# Power_Supply_V1_1.net
KiCad netlist of a schematic drawn in Altium Designer
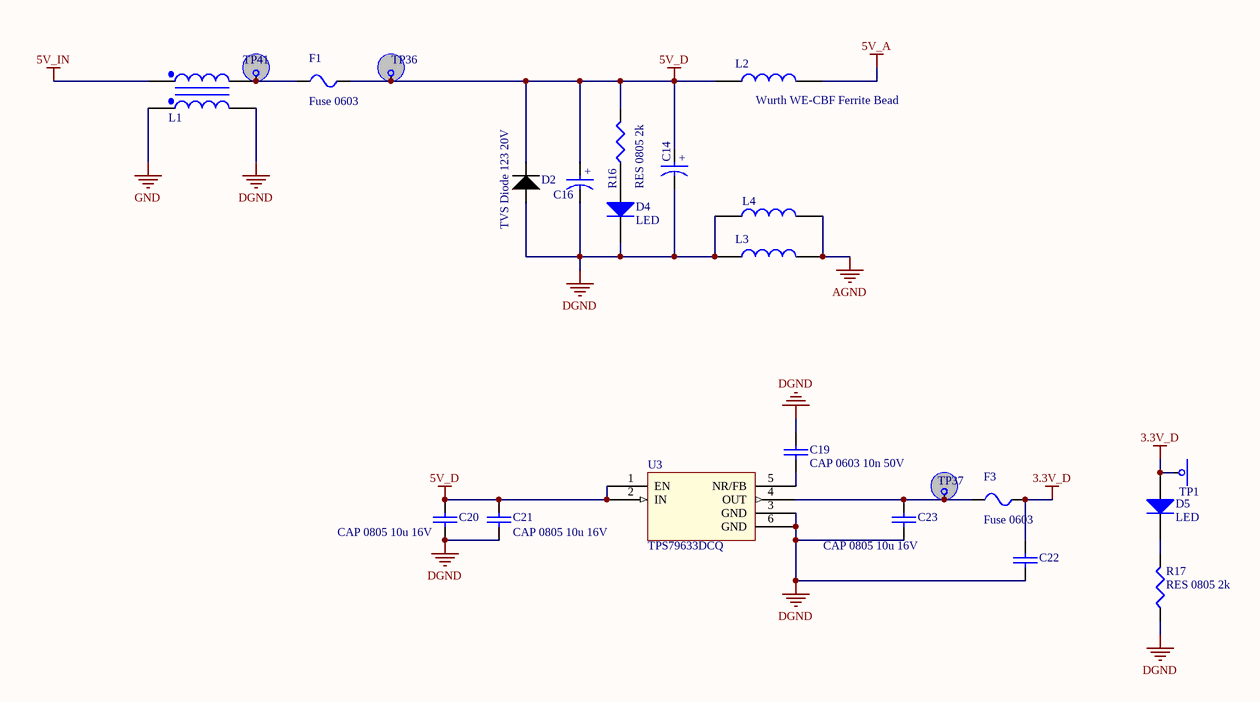
[diagram p0: Power_Supply_V1.1.SchDoc]

(export (version "E")
  (design (tool "Eeschema 10.0.6"))
  (components
    (comp (ref "C14")
      (value "Panasonic SMD aluminum cap FT V size d")
      (footprint "Panasonic TF V SMD size D cap")
      (libsource (lib "SMD_R&C_V1.0") (part "Panasonic SMD aluminum cap FT V size d"))
    )
    (comp (ref "C16")
      (value "Panasonic SMD aluminum cap FT V size d")
      (footprint "Panasonic TF V SMD size D cap")
      (libsource (lib "SMD_R&C_V1.0") (part "Panasonic SMD aluminum cap FT V size d"))
    )
    (comp (ref "C19")
      (value "CAP 0603 10n 50V")
      (footprint "CAPC1608N")
      (description "CAP 0603 TBD")
      (fields (field (name "PART#") "TBD"))
      (libsource (lib "SMD_R&C_V1.0") (part "CAP 0603 TBD"))
    )
    (comp (ref "C20")
      (value "CAP 0805 10u 16V")
      (footprint "CAPC2012N")
      (description "CAP 0805 TBD")
      (fields (field (name "PART#") "TBD"))
      (libsource (lib "SMD_R&C_V1.0") (part "CAP 0805 TBD"))
    )
    (comp (ref "C21")
      (value "CAP 0805 10u 16V")
      (footprint "CAPC2012N")
      (description "CAP 0805 TBD")
      (fields (field (name "PART#") "TBD"))
      (libsource (lib "SMD_R&C_V1.0") (part "CAP 0805 TBD"))
    )
    (comp (ref "C22")
      (value "CAP 0805 10u 16V")
      (footprint "CAPC2012N")
      (description "CAP 0805 TBD")
      (fields (field (name "PART#") "TBD"))
      (libsource (lib "SMD_R&C_V1.0") (part "CAP 0805 TBD"))
    )
    (comp (ref "C23")
      (value "CAP 0805 10u 16V")
      (footprint "CAPC2012N")
      (description "CAP 0805 TBD")
      (fields (field (name "PART#") "TBD"))
      (libsource (lib "SMD_R&C_V1.0") (part "CAP 0805 TBD"))
    )
    (comp (ref "D2")
      (value "TVS Diode 123 20V")
      (footprint "SOD-123")
      (libsource (lib "Power_Inductor&Diode_V1.0") (part "TVS Diode TBD"))
    )
    (comp (ref "D4")
      (value "LED")
      (footprint "LED1608N")
      (fields (field (name "PART#") "475-1406-1-ND"))
      (libsource (lib "SMD_R&C_V1.0") (part "LED"))
    )
    (comp (ref "D5")
      (value "LED")
      (footprint "LED1608N")
      (fields (field (name "PART#") "475-1406-1-ND"))
      (libsource (lib "SMD_R&C_V1.0") (part "LED"))
    )
    (comp (ref "F1")
      (value "Fuse 0603")
      (footprint "RES1608N")
      (libsource (lib "SMD_R&C_V1.0") (part "Fuse 0603"))
    )
    (comp (ref "F3")
      (value "Fuse 0603")
      (footprint "RES1608N")
      (libsource (lib "SMD_R&C_V1.0") (part "Fuse 0603"))
    )
    (comp (ref "L1")
      (value "Wurth")
      (footprint "WURTH WE-SL5")
      (description "Wurth WE-SL5 Common Mode Choke")
      (fields (field (name "PART NUMBER") "811-1253-ND") (field (name "MANUFACTURER PART NUMBER") "51105C"))
      (libsource (lib "Aarons_Library") (part "Wurth WE-SL5"))
    )
    (comp (ref "L2")
      (value "Wurth WE-CBF Ferrite Bead")
      (footprint "Wurth WE-CBF")
      (description "Wurth WE-CBF Ferrite Bead 2A 0.15Ohm")
      (fields (field (name "PART NUMBER") "811-1253-ND") (field (name "MANUFACTURER PART NUMBER") "51105C"))
      (libsource (lib "Aarons_Library") (part "Wurth WE-CBF"))
    )
    (comp (ref "L3")
      (value "Wurth WE-CBF Ferrite Bead")
      (footprint "Wurth WE-CBF")
      (description "Wurth WE-CBF Ferrite Bead 2A 0.15Ohm")
      (fields (field (name "PART NUMBER") "811-1253-ND") (field (name "MANUFACTURER PART NUMBER") "51105C"))
      (libsource (lib "Aarons_Library") (part "Wurth WE-CBF"))
    )
    (comp (ref "L4")
      (value "Wurth WE-CBF Ferrite Bead")
      (footprint "Wurth WE-CBF")
      (description "Wurth WE-CBF Ferrite Bead 2A 0.15Ohm")
      (fields (field (name "PART NUMBER") "811-1253-ND") (field (name "MANUFACTURER PART NUMBER") "51105C"))
      (libsource (lib "Aarons_Library") (part "Wurth WE-CBF"))
    )
    (comp (ref "R16")
      (value "RES 0805 2k")
      (footprint "RES2012N")
      (fields (field (name "PART#") "TBD"))
      (libsource (lib "SMD_R&C_V1.0") (part "RES 0805 TBD"))
    )
    (comp (ref "R17")
      (value "RES 0805 2k")
      (footprint "RES2012N")
      (fields (field (name "PART#") "TBD"))
      (libsource (lib "SMD_R&C_V1.0") (part "RES 0805 TBD"))
    )
    (comp (ref "TP1")
      (value "TEST_POINT_HOOK")
      (footprint "Keystone 5000")
      (libsource (lib "") (part "TEST_POINT_HOOK_1"))
    )
    (comp (ref "TP36")
      (value "*")
      (footprint "Keystone 5000")
      (libsource (lib "Aarons_Library") (part "TEST_POINT_HOOK"))
    )
    (comp (ref "TP37")
      (value "*")
      (footprint "Keystone 5000")
      (libsource (lib "Aarons_Library") (part "TEST_POINT_HOOK"))
    )
    (comp (ref "TP41")
      (value "TEST_POINT_HOOK")
      (footprint "Keystone 5000")
      (libsource (lib "Aarons_Library") (part "TEST_POINT_HOOK"))
    )
    (comp (ref "U3")
      (value "TPS79633DCQ")
      (footprint "SOT-223-6")
      (description "Single Output LDO, 1.0A, Fixed(3.3V), Low Noise, High PSRR")
      (fields
        (field (name "MANUFACTURER_PART_NUMBER") "tps79633_dcq_6")
        (field (name "GENERIC_PART_NUMBER") "TPS79633")
      )
      (libsource (lib "Power_Supply V1.0") (part "TPS79633"))
    )
  )
  (nets
    (net (code "1") (name "3.3V_D") (class "Default")
      (node (ref "C22") (pin "1") (pintype "passive"))
      (node (ref "D5") (pin "1") (pintype "passive"))
      (node (ref "F3") (pin "2") (pinfunction "2_2") (pintype "passive"))
      (node (ref "TP1") (pin "1") (pinfunction "1_1") (pintype "passive"))
    )
    (net (code "2") (name "5V_A") (class "Default")
      (node (ref "L2") (pin "2") (pinfunction "2_2") (pintype "passive"))
    )
    (net (code "3") (name "5V_D") (class "Default")
      (node (ref "C14") (pin "1") (pintype "passive"))
      (node (ref "C16") (pin "1") (pintype "passive"))
      (node (ref "C20") (pin "1") (pintype "passive"))
      (node (ref "C21") (pin "1") (pintype "passive"))
      (node (ref "D2") (pin "1") (pinfunction "C_1") (pintype "passive"))
      (node (ref "F1") (pin "2") (pinfunction "2_2") (pintype "passive"))
      (node (ref "L2") (pin "1") (pinfunction "1_1") (pintype "passive"))
      (node (ref "R16") (pin "2") (pinfunction "2_2") (pintype "passive"))
      (node (ref "TP36") (pin "1") (pinfunction "1_1") (pintype "passive"))
      (node (ref "U3") (pin "1") (pinfunction "EN_1") (pintype "passive"))
      (node (ref "U3") (pin "2") (pinfunction "IN_2") (pintype "input"))
    )
    (net (code "4") (name "5V_IN") (class "Default")
      (node (ref "L1") (pin "1") (pinfunction "1_1") (pintype "passive"))
    )
    (net (code "5") (name "AGND") (class "Default")
      (node (ref "L3") (pin "2") (pinfunction "2_2") (pintype "passive"))
      (node (ref "L4") (pin "2") (pinfunction "2_2") (pintype "passive"))
    )
    (net (code "6") (name "DGND") (class "Default")
      (node (ref "C14") (pin "2") (pintype "passive"))
      (node (ref "C16") (pin "2") (pintype "passive"))
      (node (ref "C19") (pin "1") (pintype "passive"))
      (node (ref "C20") (pin "2") (pintype "passive"))
      (node (ref "C21") (pin "2") (pintype "passive"))
      (node (ref "C22") (pin "2") (pintype "passive"))
      (node (ref "C23") (pin "2") (pintype "passive"))
      (node (ref "D2") (pin "2") (pinfunction "A_2") (pintype "passive"))
      (node (ref "D4") (pin "2") (pintype "passive"))
      (node (ref "L1") (pin "3") (pinfunction "3_3") (pintype "passive"))
      (node (ref "L3") (pin "1") (pinfunction "1_1") (pintype "passive"))
      (node (ref "L4") (pin "1") (pinfunction "1_1") (pintype "passive"))
      (node (ref "R17") (pin "1") (pinfunction "1_1") (pintype "passive"))
      (node (ref "U3") (pin "3") (pinfunction "GND_3") (pintype "power_in"))
      (node (ref "U3") (pin "6") (pinfunction "GND_6") (pintype "power_in"))
    )
    (net (code "7") (name "GND") (class "Default")
      (node (ref "L1") (pin "4") (pinfunction "4_4") (pintype "passive"))
    )
    (net (code "8") (name "Net-(D4-Pad1)") (class "Default")
      (node (ref "D4") (pin "1") (pintype "passive"))
      (node (ref "R16") (pin "1") (pinfunction "1_1") (pintype "passive"))
    )
    (net (code "9") (name "Net-(D5-Pad2)") (class "Default")
      (node (ref "D5") (pin "2") (pintype "passive"))
      (node (ref "R17") (pin "2") (pinfunction "2_2") (pintype "passive"))
    )
    (net (code "10") (name "Net-(F1-Pad1)") (class "Default")
      (node (ref "F1") (pin "1") (pinfunction "1_1") (pintype "passive"))
      (node (ref "L1") (pin "2") (pinfunction "2_2") (pintype "passive"))
      (node (ref "TP41") (pin "1") (pinfunction "1_1") (pintype "passive"))
    )
    (net (code "11") (name "Net-(U3-NR{slash}FB)") (class "Default")
      (node (ref "C19") (pin "2") (pintype "passive"))
      (node (ref "U3") (pin "5") (pinfunction "NR/FB_5") (pintype "passive"))
    )
    (net (code "12") (name "Net-(U3-OUT)") (class "Default")
      (node (ref "C23") (pin "1") (pintype "passive"))
      (node (ref "F3") (pin "1") (pinfunction "1_1") (pintype "passive"))
      (node (ref "TP37") (pin "1") (pinfunction "1_1") (pintype "passive"))
      (node (ref "U3") (pin "4") (pinfunction "OUT_4") (pintype "output"))
    )
  )
)
